# cpu_board.net
KiCad netlist of a schematic drawn in Altium Designer
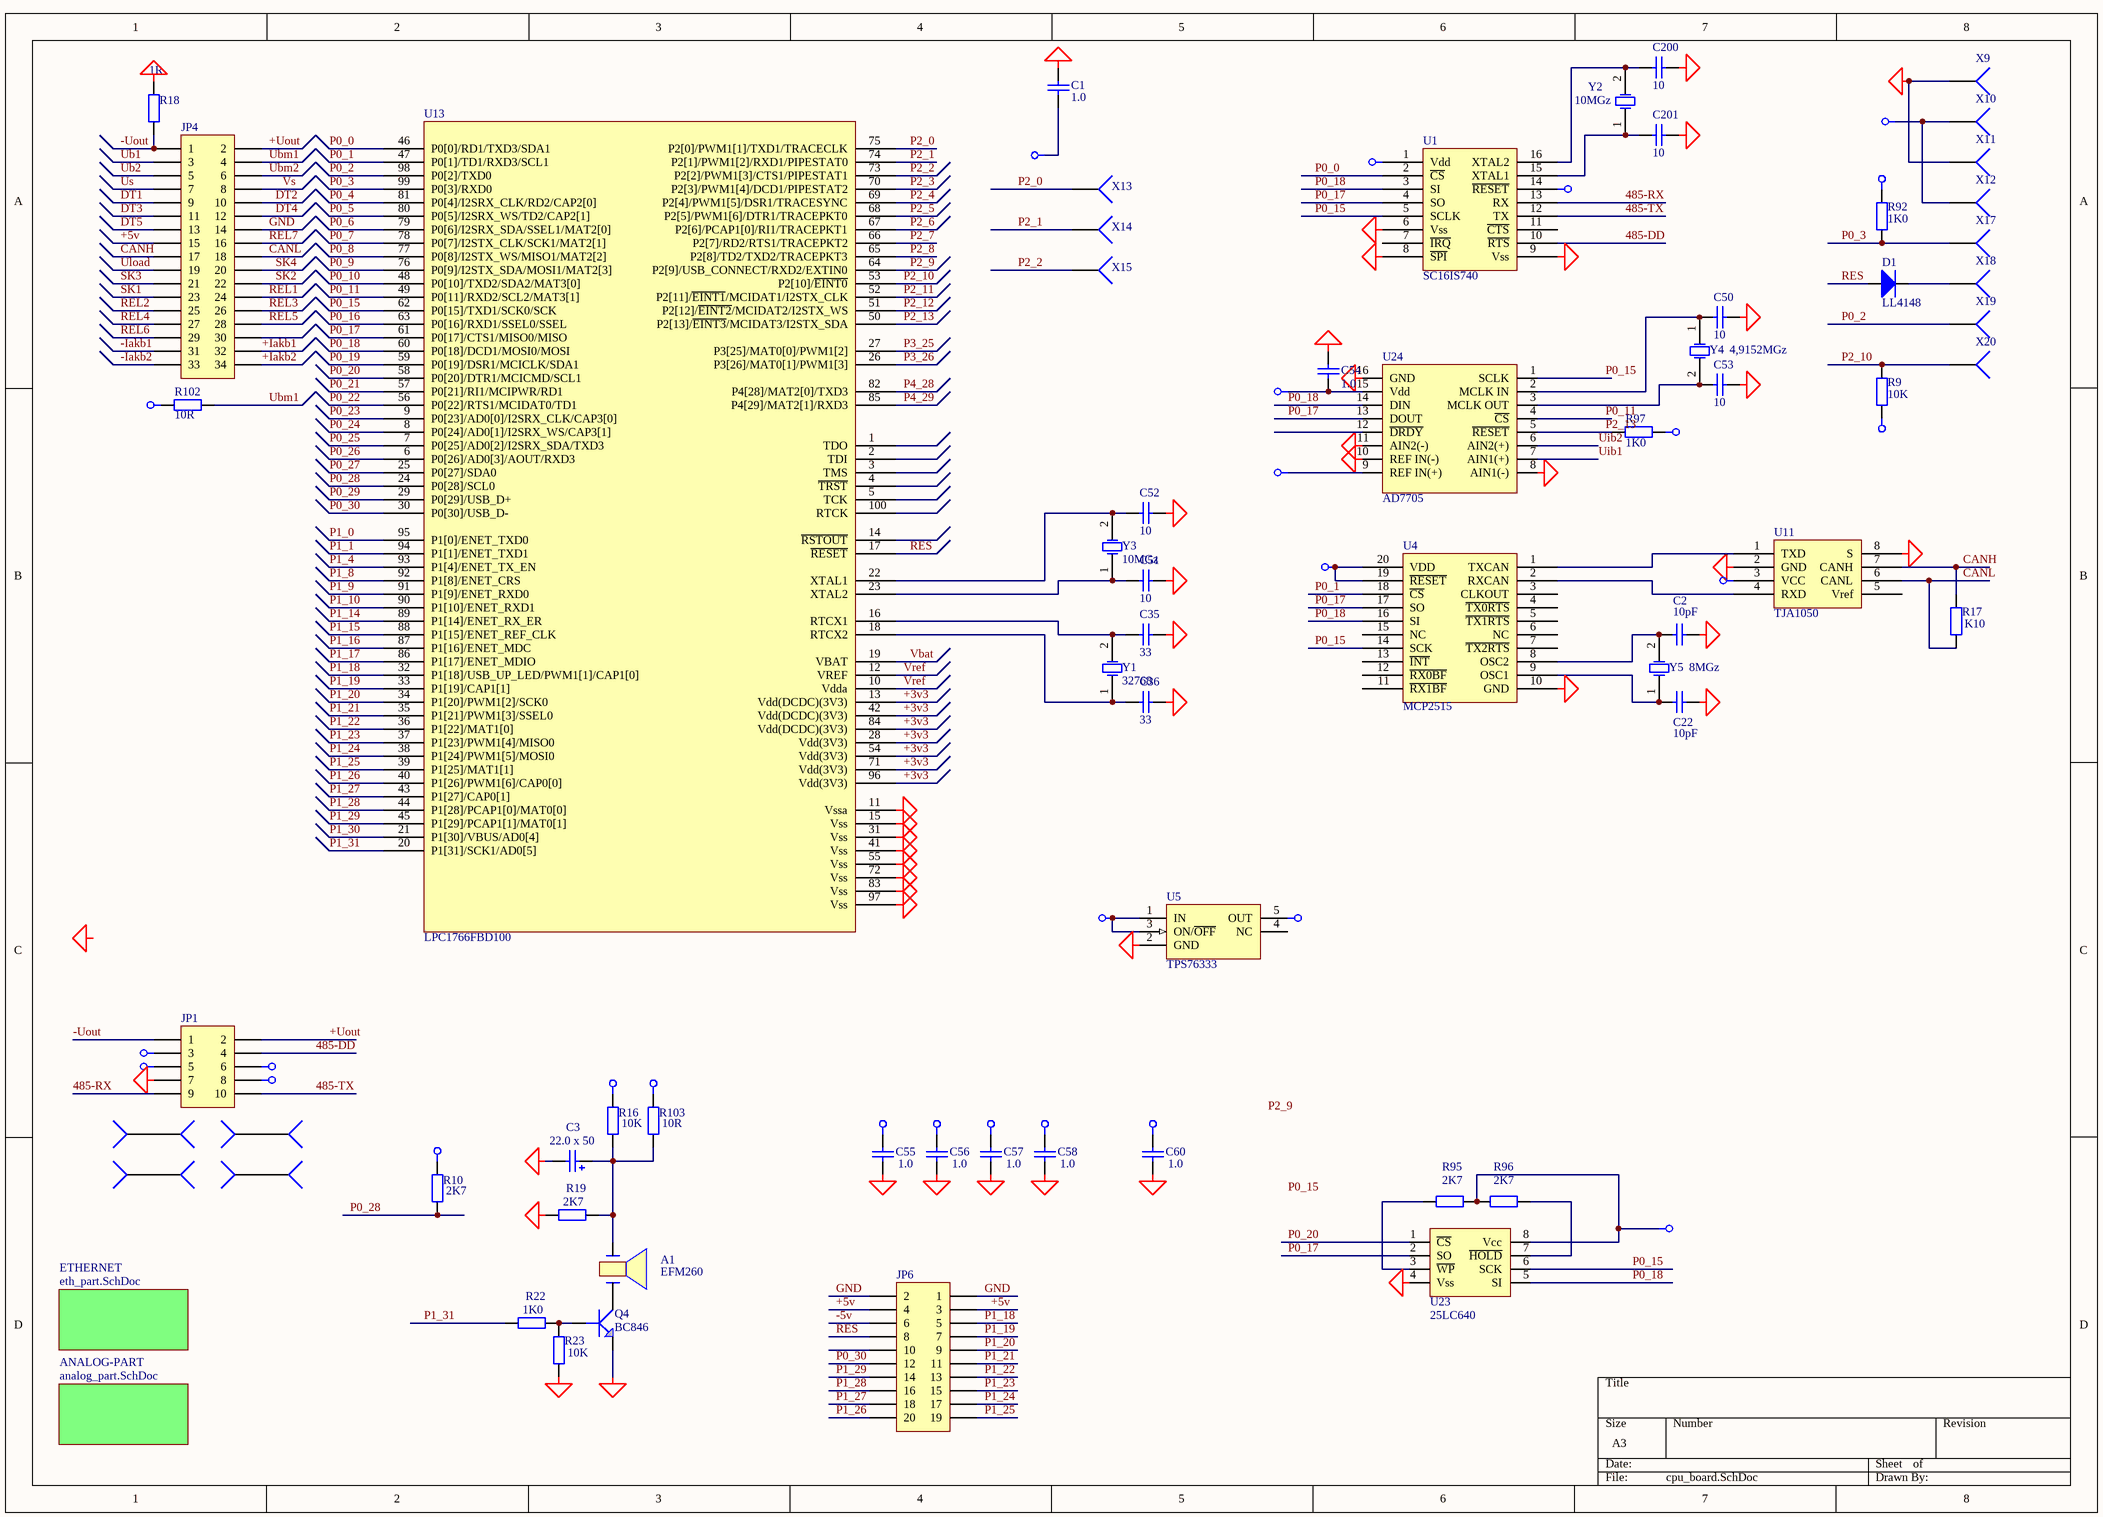
[diagram p0: cpu_board.SchDoc]

(export (version "E")
  (design (tool "Eeschema 10.0.6"))
  (components
    (comp (ref "A1")
      (value "EFM260")
      (footprint "Pjezo15")
      (description "Beeper")
      (libsource (lib "PAL") (part "PJEZ0"))
    )
    (comp (ref "C1")
      (value "1.0")
      (footprint "_1206")
      (description "Capacitor")
      (fields (field (name "MANUFACTURER") "Generic Components") (field (name "PUBLISHER") "Altium Limited"))
      (libsource (lib "Miscellaneous Devices") (part "Cap Semi"))
    )
    (comp (ref "C2")
      (value "Cap Semi")
      (footprint "_1206")
      (description "Capacitor (Semiconductor SIM Model)")
      (fields
        (field (name "MANUFACTURER") "Generic Components")
        (field (name "ALTIUM_VALUE") "10pF")
        (field (name "PUBLISHER") "Altium Limited")
      )
      (libsource (lib "Miscellaneous Devices") (part "Cap Semi"))
    )
    (comp (ref "C3")
      (value "22.0 x 50")
      (footprint "el3")
      (description "Polarized Capacitor (Radial)")
      (fields (field (name "MANUFACTURER") "Generic Components") (field (name "PUBLISHER") "Altium Limited"))
      (libsource (lib "PAL") (part "Cap Pol1"))
    )
    (comp (ref "C22")
      (value "Cap Semi")
      (footprint "_1206")
      (description "Capacitor (Semiconductor SIM Model)")
      (fields
        (field (name "MANUFACTURER") "Generic Components")
        (field (name "ALTIUM_VALUE") "10pF")
        (field (name "PUBLISHER") "Altium Limited")
      )
      (libsource (lib "Miscellaneous Devices") (part "Cap Semi"))
    )
    (comp (ref "C35")
      (value "33")
      (footprint "_1206")
      (description "Capacitor (Semiconductor SIM Model)")
      (fields (field (name "MANUFACTURER") "Generic Components") (field (name "PUBLISHER") "Altium Limited"))
      (libsource (lib "Miscellaneous Devices") (part "Cap Semi"))
    )
    (comp (ref "C36")
      (value "33")
      (footprint "_1206")
      (description "Capacitor (Semiconductor SIM Model)")
      (fields (field (name "MANUFACTURER") "Generic Components") (field (name "PUBLISHER") "Altium Limited"))
      (libsource (lib "Miscellaneous Devices") (part "Cap Semi"))
    )
    (comp (ref "C50")
      (value "10")
      (footprint "_1206")
      (description "Capacitor")
      (fields (field (name "MANUFACTURER") "Generic Components") (field (name "PUBLISHER") "Altium Limited"))
      (libsource (lib "") (part "Cap Semi_1"))
    )
    (comp (ref "C51")
      (value "10")
      (footprint "_1206")
      (description "Capacitor")
      (fields (field (name "MANUFACTURER") "Generic Components") (field (name "PUBLISHER") "Altium Limited"))
      (libsource (lib "Miscellaneous Devices") (part "Cap Semi"))
    )
    (comp (ref "C52")
      (value "10")
      (footprint "_1206")
      (description "Capacitor")
      (fields (field (name "MANUFACTURER") "Generic Components") (field (name "PUBLISHER") "Altium Limited"))
      (libsource (lib "Miscellaneous Devices") (part "Cap Semi"))
    )
    (comp (ref "C53")
      (value "10")
      (footprint "_1206")
      (description "Capacitor")
      (fields (field (name "MANUFACTURER") "Generic Components") (field (name "PUBLISHER") "Altium Limited"))
      (libsource (lib "") (part "Cap Semi_1"))
    )
    (comp (ref "C54")
      (value "1.0")
      (footprint "_1206")
      (description "Capacitor")
      (fields (field (name "MANUFACTURER") "Generic Components") (field (name "PUBLISHER") "Altium Limited"))
      (libsource (lib "Miscellaneous Devices") (part "Cap Semi"))
    )
    (comp (ref "C55")
      (value "1.0")
      (footprint "_1206")
      (description "Capacitor")
      (fields (field (name "MANUFACTURER") "Generic Components") (field (name "PUBLISHER") "Altium Limited"))
      (libsource (lib "Miscellaneous Devices") (part "Cap Semi"))
    )
    (comp (ref "C56")
      (value "1.0")
      (footprint "_1206")
      (description "Capacitor")
      (fields (field (name "MANUFACTURER") "Generic Components") (field (name "PUBLISHER") "Altium Limited"))
      (libsource (lib "Miscellaneous Devices") (part "Cap Semi"))
    )
    (comp (ref "C57")
      (value "1.0")
      (footprint "_1206")
      (description "Capacitor")
      (fields (field (name "MANUFACTURER") "Generic Components") (field (name "PUBLISHER") "Altium Limited"))
      (libsource (lib "Miscellaneous Devices") (part "Cap Semi"))
    )
    (comp (ref "C58")
      (value "1.0")
      (footprint "_1206")
      (description "Capacitor")
      (fields (field (name "MANUFACTURER") "Generic Components") (field (name "PUBLISHER") "Altium Limited"))
      (libsource (lib "Miscellaneous Devices") (part "Cap Semi"))
    )
    (comp (ref "C60")
      (value "1.0")
      (footprint "_1206")
      (description "Capacitor")
      (fields (field (name "MANUFACTURER") "Generic Components") (field (name "PUBLISHER") "Altium Limited"))
      (libsource (lib "Miscellaneous Devices") (part "Cap Semi"))
    )
    (comp (ref "C200")
      (value "10")
      (footprint "_1206")
      (description "Capacitor")
      (fields (field (name "MANUFACTURER") "Generic Components") (field (name "PUBLISHER") "Altium Limited"))
      (libsource (lib "Miscellaneous Devices") (part "Cap Semi"))
    )
    (comp (ref "C201")
      (value "10")
      (footprint "_1206")
      (description "Capacitor")
      (fields (field (name "MANUFACTURER") "Generic Components") (field (name "PUBLISHER") "Altium Limited"))
      (libsource (lib "Miscellaneous Devices") (part "Cap Semi"))
    )
    (comp (ref "D1")
      (value "LL4148")
      (footprint "_1206d")
      (description "Diode")
      (fields (field (name "MANUFACTURER") "Generic Components") (field (name "PUBLISHER") "Altium Limited"))
      (libsource (lib "PAL") (part "Diode"))
    )
    (comp (ref "JP1")
      (value "PBD-10")
      (footprint "HDR2X5")
      (description "Header, 5-Pin, Dual row")
      (fields (field (name "MANUFACTURER") "Generic Components") (field (name "PUBLISHER") "Altium Limited"))
      (libsource (lib "Miscellaneous Connectors") (part "Header 5X2"))
    )
    (comp (ref "JP4")
      (value "IDC34")
      (footprint "IDC34M")
      (description "Header, 17-Pin, Dual row")
      (fields (field (name "MANUFACTURER") "Generic Components") (field (name "PUBLISHER") "Altium Limited"))
      (libsource (lib "Miscellaneous Connectors") (part "Header 17X2"))
    )
    (comp (ref "JP6")
      (value "PBD-20")
      (footprint "HDR2X10")
      (description "Header, 10-Pin, Dual row")
      (fields (field (name "MANUFACTURER") "Generic Components") (field (name "PUBLISHER") "Altium Limited"))
      (libsource (lib "Miscellaneous Connectors") (part "Header 10X2"))
    )
    (comp (ref "Q4")
      (value "BC846")
      (footprint "SO-G3")
      (description "Bipolar transistor")
      (libsource (lib "MAIN") (part "GT122"))
    )
    (comp (ref "R9")
      (value "10K")
      (footprint "_1206")
      (description "Resistor")
      (fields (field (name "MANUFACTURER") "Generic Components") (field (name "PUBLISHER") "Altium Limited"))
      (libsource (lib "Miscellaneous Devices") (part "Res2"))
    )
    (comp (ref "R10")
      (value "2K7")
      (footprint "_1206")
      (description "Resistor")
      (fields (field (name "MANUFACTURER") "Generic Components") (field (name "PUBLISHER") "Altium Limited"))
      (libsource (lib "Miscellaneous Devices") (part "Res2"))
    )
    (comp (ref "R16")
      (value "10K")
      (footprint "_1206")
      (description "Resistor")
      (fields (field (name "MANUFACTURER") "Generic Components") (field (name "PUBLISHER") "Altium Limited"))
      (libsource (lib "Miscellaneous Devices") (part "Res2"))
    )
    (comp (ref "R17")
      (value "K10")
      (footprint "_1206")
      (description "Resistor")
      (fields (field (name "MANUFACTURER") "Generic Components") (field (name "PUBLISHER") "Altium Limited"))
      (libsource (lib "Miscellaneous Devices") (part "Res2"))
    )
    (comp (ref "R18")
      (value "1R")
      (footprint "_1206")
      (description "Resistor")
      (fields (field (name "MANUFACTURER") "Generic Components") (field (name "PUBLISHER") "Altium Limited"))
      (libsource (lib "Miscellaneous Devices") (part "Res2"))
    )
    (comp (ref "R19")
      (value "2K7")
      (footprint "_1206")
      (description "Resistor")
      (fields (field (name "MANUFACTURER") "Generic Components") (field (name "PUBLISHER") "Altium Limited"))
      (libsource (lib "") (part "Res2_1"))
    )
    (comp (ref "R22")
      (value "1K0")
      (footprint "_1206")
      (description "Resistor")
      (fields (field (name "MANUFACTURER") "Generic Components") (field (name "PUBLISHER") "Altium Limited"))
      (libsource (lib "") (part "Res2_1"))
    )
    (comp (ref "R23")
      (value "10K")
      (footprint "_1206")
      (description "Resistor")
      (fields (field (name "MANUFACTURER") "Generic Components") (field (name "PUBLISHER") "Altium Limited"))
      (libsource (lib "Miscellaneous Devices") (part "Res2"))
    )
    (comp (ref "R92")
      (value "1K0")
      (footprint "_1206")
      (description "Resistor")
      (fields (field (name "MANUFACTURER") "Generic Components") (field (name "PUBLISHER") "Altium Limited"))
      (libsource (lib "") (part "Res2_1"))
    )
    (comp (ref "R95")
      (value "2K7")
      (footprint "_1206")
      (description "Resistor")
      (fields (field (name "MANUFACTURER") "Generic Components") (field (name "PUBLISHER") "Altium Limited"))
      (libsource (lib "") (part "Res2_1"))
    )
    (comp (ref "R96")
      (value "2K7")
      (footprint "_1206")
      (description "Resistor")
      (fields (field (name "MANUFACTURER") "Generic Components") (field (name "PUBLISHER") "Altium Limited"))
      (libsource (lib "") (part "Res2_1"))
    )
    (comp (ref "R97")
      (value "1K0")
      (footprint "_1206")
      (description "Resistor")
      (fields (field (name "MANUFACTURER") "Generic Components") (field (name "PUBLISHER") "Altium Limited"))
      (libsource (lib "Miscellaneous Devices") (part "Res2"))
    )
    (comp (ref "R102")
      (value "10R")
      (footprint "_1206")
      (description "Resistor")
      (fields (field (name "MANUFACTURER") "Generic Components") (field (name "PUBLISHER") "Altium Limited"))
      (libsource (lib "") (part "Res2_2"))
    )
    (comp (ref "R103")
      (value "10R")
      (footprint "_1206")
      (description "Resistor")
      (fields (field (name "MANUFACTURER") "Generic Components") (field (name "PUBLISHER") "Altium Limited"))
      (libsource (lib "Miscellaneous Devices") (part "Res2"))
    )
    (comp (ref "U1") (value "SC16IS740") (footprint "SO-G16") (libsource (lib "PAL") (part "SC16IS740")))
    (comp (ref "U4")
      (value "MCP2515")
      (footprint "TSSO6X6-G20/D6.6")
      (libsource (lib "PAL") (part "MCP2515"))
    )
    (comp (ref "U5")
      (value "TPS76333")
      (footprint "SO-G5/P.95")
      (description "Voltage Regulator")
      (fields
        (field (name "MANUFACTURER") "National Semiconductor")
        (field (name "PUBLISHER") "Altium Limited")
      )
      (libsource (lib "NSC Power Mgt Voltage Regulator") (part "LP2980AIM5-3.3"))
    )
    (comp (ref "U11") (value "TJA1050") (footprint "SO-G8/D5") (libsource (lib "PAL") (part "TJA1050")))
    (comp (ref "U13")
      (value "LPC1766FBD100")
      (footprint "LPC2368")
      (libsource (lib "PAL") (part "LPC2368FBD100"))
    )
    (comp (ref "U23")
      (value "25LC640")
      (footprint "SO-G8/D5")
      (description "Memory")
      (libsource (lib "PAL") (part "25LC640"))
    )
    (comp (ref "U24")
      (value "AD7705")
      (footprint "SO-G16/D10.4")
      (description "ADC")
      (libsource (lib "PAL") (part "AD7705"))
    )
    (comp (ref "X9")
      (value "~")
      (footprint "PIN1")
      (description "Socket")
      (fields (field (name "MANUFACTURER") "Generic Components") (field (name "PUBLISHER") "Altium Limited"))
      (libsource (lib "Miscellaneous Connectors") (part "Socket"))
    )
    (comp (ref "X10")
      (value "~")
      (footprint "PIN1")
      (description "Socket")
      (fields (field (name "MANUFACTURER") "Generic Components") (field (name "PUBLISHER") "Altium Limited"))
      (libsource (lib "Miscellaneous Connectors") (part "Socket"))
    )
    (comp (ref "X11")
      (value "~")
      (footprint "PIN1")
      (description "Socket")
      (fields (field (name "MANUFACTURER") "Generic Components") (field (name "PUBLISHER") "Altium Limited"))
      (libsource (lib "Miscellaneous Connectors") (part "Socket"))
    )
    (comp (ref "X12")
      (value "~")
      (footprint "PIN1")
      (description "Socket")
      (fields (field (name "MANUFACTURER") "Generic Components") (field (name "PUBLISHER") "Altium Limited"))
      (libsource (lib "Miscellaneous Connectors") (part "Socket"))
    )
    (comp (ref "X13")
      (value "~")
      (footprint "PIN1")
      (description "Socket")
      (fields (field (name "MANUFACTURER") "Generic Components") (field (name "PUBLISHER") "Altium Limited"))
      (libsource (lib "Miscellaneous Connectors") (part "Socket"))
    )
    (comp (ref "X14")
      (value "~")
      (footprint "PIN1")
      (description "Socket")
      (fields (field (name "MANUFACTURER") "Generic Components") (field (name "PUBLISHER") "Altium Limited"))
      (libsource (lib "Miscellaneous Connectors") (part "Socket"))
    )
    (comp (ref "X15")
      (value "~")
      (footprint "PIN1")
      (description "Socket")
      (fields (field (name "MANUFACTURER") "Generic Components") (field (name "PUBLISHER") "Altium Limited"))
      (libsource (lib "Miscellaneous Connectors") (part "Socket"))
    )
    (comp (ref "X16")
      (value "~")
      (footprint "PIN1")
      (description "Socket")
      (fields (field (name "MANUFACTURER") "Generic Components") (field (name "PUBLISHER") "Altium Limited"))
      (libsource (lib "Miscellaneous Connectors") (part "Socket"))
    )
    (comp (ref "X17")
      (value "~")
      (footprint "PIN1")
      (description "Socket")
      (fields (field (name "MANUFACTURER") "Generic Components") (field (name "PUBLISHER") "Altium Limited"))
      (libsource (lib "Miscellaneous Connectors") (part "Socket"))
    )
    (comp (ref "X18")
      (value "~")
      (footprint "PIN1")
      (description "Socket")
      (fields (field (name "MANUFACTURER") "Generic Components") (field (name "PUBLISHER") "Altium Limited"))
      (libsource (lib "Miscellaneous Connectors") (part "Socket"))
    )
    (comp (ref "X19")
      (value "~")
      (footprint "PIN1")
      (description "Socket")
      (fields (field (name "MANUFACTURER") "Generic Components") (field (name "PUBLISHER") "Altium Limited"))
      (libsource (lib "Miscellaneous Connectors") (part "Socket"))
    )
    (comp (ref "X20")
      (value "~")
      (footprint "PIN1")
      (description "Socket")
      (fields (field (name "MANUFACTURER") "Generic Components") (field (name "PUBLISHER") "Altium Limited"))
      (libsource (lib "Miscellaneous Connectors") (part "Socket"))
    )
    (comp (ref "X21")
      (value "~")
      (footprint "PIN1")
      (description "Socket")
      (fields (field (name "MANUFACTURER") "Generic Components") (field (name "PUBLISHER") "Altium Limited"))
      (libsource (lib "Miscellaneous Connectors") (part "Socket"))
    )
    (comp (ref "X22")
      (value "~")
      (footprint "PIN1")
      (description "Socket")
      (fields (field (name "MANUFACTURER") "Generic Components") (field (name "PUBLISHER") "Altium Limited"))
      (libsource (lib "Miscellaneous Connectors") (part "Socket"))
    )
    (comp (ref "X23")
      (value "~")
      (footprint "PIN1")
      (description "Socket")
      (fields (field (name "MANUFACTURER") "Generic Components") (field (name "PUBLISHER") "Altium Limited"))
      (libsource (lib "Miscellaneous Connectors") (part "Socket"))
    )
    (comp (ref "X24")
      (value "~")
      (footprint "PIN1")
      (description "Socket")
      (fields (field (name "MANUFACTURER") "Generic Components") (field (name "PUBLISHER") "Altium Limited"))
      (libsource (lib "Miscellaneous Connectors") (part "Socket"))
    )
    (comp (ref "X25")
      (value "~")
      (footprint "PIN1")
      (description "Socket")
      (fields (field (name "MANUFACTURER") "Generic Components") (field (name "PUBLISHER") "Altium Limited"))
      (libsource (lib "Miscellaneous Connectors") (part "Socket"))
    )
    (comp (ref "X26")
      (value "~")
      (footprint "PIN1")
      (description "Socket")
      (fields (field (name "MANUFACTURER") "Generic Components") (field (name "PUBLISHER") "Altium Limited"))
      (libsource (lib "Miscellaneous Connectors") (part "Socket"))
    )
    (comp (ref "X27")
      (value "~")
      (footprint "PIN1")
      (description "Socket")
      (fields (field (name "MANUFACTURER") "Generic Components") (field (name "PUBLISHER") "Altium Limited"))
      (libsource (lib "Miscellaneous Connectors") (part "Socket"))
    )
    (comp (ref "Y1")
      (value "32768")
      (footprint "QWARZ2")
      (description "Crystal Oscillator")
      (fields (field (name "MANUFACTURER") "Generic Components") (field (name "PUBLISHER") "Altium Limited"))
      (libsource (lib "Miscellaneous Devices") (part "XTAL"))
    )
    (comp (ref "Y2")
      (value "10MGz")
      (footprint "QWARZ1")
      (description "Crystal Oscillator")
      (fields (field (name "MANUFACTURER") "Generic Components") (field (name "PUBLISHER") "Altium Limited"))
      (libsource (lib "Miscellaneous Devices") (part "XTAL"))
    )
    (comp (ref "Y3")
      (value "10MGz")
      (footprint "QWARZ1")
      (description "Crystal Oscillator")
      (fields (field (name "MANUFACTURER") "Generic Components") (field (name "PUBLISHER") "Altium Limited"))
      (libsource (lib "Miscellaneous Devices") (part "XTAL"))
    )
    (comp (ref "Y4")
      (value "4,9152MGz")
      (footprint "QWARZ1")
      (description "Crystal Oscillator")
      (fields (field (name "MANUFACTURER") "Generic Components") (field (name "PUBLISHER") "Altium Limited"))
      (libsource (lib "") (part "XTAL_1"))
    )
    (comp (ref "Y5")
      (value "8MGz")
      (footprint "QWARZ1")
      (description "Crystal Oscillator")
      (fields (field (name "MANUFACTURER") "Generic Components") (field (name "PUBLISHER") "Altium Limited"))
      (libsource (lib "Miscellaneous Devices") (part "XTAL"))
    )
  )
  (nets
    (net (code "1") (name "+3v3") (class "Default")
      (node (ref "C1") (pin "1") (pinfunction "1_1") (pintype "passive"))
      (node (ref "C58") (pin "2") (pinfunction "2_2") (pintype "passive"))
      (node (ref "JP1") (pin "3") (pinfunction "3_3") (pintype "passive"))
      (node (ref "R10") (pin "2") (pinfunction "2_2") (pintype "passive"))
      (node (ref "R9") (pin "1") (pinfunction "1_1") (pintype "passive"))
      (node (ref "R92") (pin "2") (pinfunction "2_2") (pintype "passive"))
      (node (ref "U13") (pin "13") (pinfunction "Vdd(DCDC)(3V3)_13") (pintype "passive"))
      (node (ref "U13") (pin "28") (pinfunction "Vdd(3V3)_28") (pintype "passive"))
      (node (ref "U13") (pin "42") (pinfunction "Vdd(DCDC)(3V3)_42") (pintype "passive"))
      (node (ref "U13") (pin "54") (pinfunction "Vdd(3V3)_54") (pintype "passive"))
      (node (ref "U13") (pin "71") (pinfunction "Vdd(3V3)_71") (pintype "passive"))
      (node (ref "U13") (pin "84") (pinfunction "Vdd(DCDC)(3V3)_84") (pintype "passive"))
      (node (ref "U13") (pin "96") (pinfunction "Vdd(3V3)_96") (pintype "passive"))
    )
    (net (code "2") (name "+5v") (class "Default")
      (node (ref "C54") (pin "2") (pinfunction "2_2") (pintype "passive"))
      (node (ref "C55") (pin "2") (pinfunction "2_2") (pintype "passive"))
      (node (ref "C57") (pin "2") (pinfunction "2_2") (pintype "passive"))
      (node (ref "C60") (pin "2") (pinfunction "2_2") (pintype "passive"))
      (node (ref "JP1") (pin "5") (pinfunction "5_5") (pintype "passive"))
      (node (ref "JP4") (pin "15") (pinfunction "15_15") (pintype "passive"))
      (node (ref "JP6") (pin "3") (pinfunction "3_3") (pintype "passive"))
      (node (ref "JP6") (pin "4") (pinfunction "4_4") (pintype "passive"))
      (node (ref "R103") (pin "2") (pinfunction "2_2") (pintype "passive"))
      (node (ref "R95") (pin "2") (pinfunction "2_2") (pintype "passive"))
      (node (ref "R96") (pin "1") (pinfunction "1_1") (pintype "passive"))
      (node (ref "R97") (pin "2") (pinfunction "2_2") (pintype "passive"))
      (node (ref "U1") (pin "1") (pinfunction "Vdd_1") (pintype "passive"))
      (node (ref "U1") (pin "14") (pinfunction "~{RESET}_14") (pintype "passive"))
      (node (ref "U11") (pin "3") (pinfunction "VCC_3") (pintype "passive"))
      (node (ref "U23") (pin "8") (pinfunction "Vcc_8") (pintype "passive"))
      (node (ref "U24") (pin "15") (pinfunction "Vdd_15") (pintype "passive"))
      (node (ref "U4") (pin "19") (pinfunction "~{RESET}_19") (pintype "passive"))
      (node (ref "U4") (pin "20") (pinfunction "VDD_20") (pintype "passive"))
      (node (ref "U5") (pin "1") (pinfunction "IN_1") (pintype "power_in"))
      (node (ref "U5") (pin "3") (pinfunction "ON/~{OFF}_3") (pintype "input"))
      (node (ref "X10") (pin "1") (pinfunction "1_1") (pintype "passive"))
      (node (ref "X12") (pin "1") (pinfunction "1_1") (pintype "passive"))
    )
    (net (code "3") (name "+Uout") (class "Default")
      (node (ref "JP1") (pin "2") (pinfunction "2_2") (pintype "passive"))
      (node (ref "JP4") (pin "2") (pinfunction "2_2") (pintype "passive"))
      (node (ref "R102") (pin "2") (pinfunction "2_2") (pintype "passive"))
      (node (ref "R16") (pin "2") (pinfunction "2_2") (pintype "passive"))
    )
    (net (code "4") (name "-5v") (class "Default")
      (node (ref "C56") (pin "2") (pinfunction "2_2") (pintype "passive"))
      (node (ref "JP1") (pin "8") (pinfunction "8_8") (pintype "passive"))
      (node (ref "JP6") (pin "6") (pinfunction "6_6") (pintype "passive"))
    )
    (net (code "5") (name "/+Iakb1") (class "Default")
      (node (ref "JP4") (pin "32") (pinfunction "32_32") (pintype "passive"))
    )
    (net (code "6") (name "/+Iakb2") (class "Default")
      (node (ref "JP4") (pin "34") (pinfunction "34_34") (pintype "passive"))
    )
    (net (code "7") (name "/-Iakb1") (class "Default")
      (node (ref "JP4") (pin "31") (pinfunction "31_31") (pintype "passive"))
    )
    (net (code "8") (name "/-Iakb2") (class "Default")
      (node (ref "JP4") (pin "33") (pinfunction "33_33") (pintype "passive"))
    )
    (net (code "9") (name "/-Uout") (class "Default")
      (node (ref "JP1") (pin "1") (pinfunction "1_1") (pintype "passive"))
      (node (ref "JP4") (pin "1") (pinfunction "1_1") (pintype "passive"))
      (node (ref "R18") (pin "1") (pinfunction "1_1") (pintype "passive"))
    )
    (net (code "10") (name "/485-DD") (class "Default")
      (node (ref "JP1") (pin "4") (pinfunction "4_4") (pintype "passive"))
      (node (ref "U1") (pin "10") (pinfunction "~{RTS}_10") (pintype "passive"))
    )
    (net (code "11") (name "/485-RX") (class "Default")
      (node (ref "JP1") (pin "9") (pinfunction "9_9") (pintype "passive"))
      (node (ref "U1") (pin "13") (pinfunction "RX_13") (pintype "passive"))
    )
    (net (code "12") (name "/485-TX") (class "Default")
      (node (ref "JP1") (pin "10") (pinfunction "10_10") (pintype "passive"))
      (node (ref "U1") (pin "12") (pinfunction "TX_12") (pintype "passive"))
    )
    (net (code "13") (name "/CANH") (class "Default")
      (node (ref "JP4") (pin "17") (pinfunction "17_17") (pintype "passive"))
      (node (ref "R17") (pin "2") (pinfunction "2_2") (pintype "passive"))
      (node (ref "U11") (pin "7") (pinfunction "CANH_7") (pintype "passive"))
    )
    (net (code "14") (name "/CANL") (class "Default")
      (node (ref "JP4") (pin "18") (pinfunction "18_18") (pintype "passive"))
      (node (ref "R17") (pin "1") (pinfunction "1_1") (pintype "passive"))
      (node (ref "U11") (pin "6") (pinfunction "CANL_6") (pintype "passive"))
    )
    (net (code "15") (name "/DT1") (class "Default")
      (node (ref "JP4") (pin "9") (pinfunction "9_9") (pintype "passive"))
    )
    (net (code "16") (name "/DT2") (class "Default")
      (node (ref "JP4") (pin "10") (pinfunction "10_10") (pintype "passive"))
    )
    (net (code "17") (name "/DT3") (class "Default")
      (node (ref "JP4") (pin "11") (pinfunction "11_11") (pintype "passive"))
    )
    (net (code "18") (name "/DT4") (class "Default")
      (node (ref "JP4") (pin "12") (pinfunction "12_12") (pintype "passive"))
    )
    (net (code "19") (name "/DT5") (class "Default")
      (node (ref "JP4") (pin "13") (pinfunction "13_13") (pintype "passive"))
    )
    (net (code "20") (name "/P0_0") (class "Default")
      (node (ref "U1") (pin "2") (pinfunction "~{CS}_2") (pintype "passive"))
      (node (ref "U13") (pin "46") (pinfunction "P0[0]/RD1/TXD3/SDA1_46") (pintype "passive"))
    )
    (net (code "21") (name "/P0_1") (class "Default")
      (node (ref "U13") (pin "47") (pinfunction "P0[1]/TD1/RXD3/SCL1_47") (pintype "passive"))
      (node (ref "U4") (pin "18") (pinfunction "~{CS}_18") (pintype "passive"))
    )
    (net (code "22") (name "/P0_2") (class "Default")
      (node (ref "U13") (pin "98") (pinfunction "P0[2]/TXD0_98") (pintype "passive"))
      (node (ref "X19") (pin "1") (pinfunction "1_1") (pintype "passive"))
    )
    (net (code "23") (name "/P0_3") (class "Default")
      (node (ref "R92") (pin "1") (pinfunction "1_1") (pintype "passive"))
      (node (ref "U13") (pin "99") (pinfunction "P0[3]/RXD0_99") (pintype "passive"))
      (node (ref "X17") (pin "1") (pinfunction "1_1") (pintype "passive"))
    )
    (net (code "24") (name "/P0_4") (class "Default")
      (node (ref "U13") (pin "81") (pinfunction "P0[4]/I2SRX_CLK/RD2/CAP2[0]_81") (pintype "passive"))
    )
    (net (code "25") (name "/P0_5") (class "Default")
      (node (ref "U13") (pin "80") (pinfunction "P0[5]/I2SRX_WS/TD2/CAP2[1]_80") (pintype "passive"))
    )
    (net (code "26") (name "/P0_6") (class "Default")
      (node (ref "U13") (pin "79") (pinfunction "P0[6]/I2SRX_SDA/SSEL1/MAT2[0]_79") (pintype "passive"))
    )
    (net (code "27") (name "/P0_7") (class "Default")
      (node (ref "U13") (pin "78") (pinfunction "P0[7]/I2STX_CLK/SCK1/MAT2[1]_78") (pintype "passive"))
    )
    (net (code "28") (name "/P0_8") (class "Default")
      (node (ref "U13") (pin "77") (pinfunction "P0[8]/I2STX_WS/MISO1/MAT2[2]_77") (pintype "passive"))
    )
    (net (code "29") (name "/P0_9") (class "Default")
      (node (ref "U13") (pin "76") (pinfunction "P0[9]/I2STX_SDA/MOSI1/MAT2[3]_76") (pintype "passive"))
    )
    (net (code "30") (name "/P0_10") (class "Default")
      (node (ref "U13") (pin "48") (pinfunction "P0[10]/TXD2/SDA2/MAT3[0]_48") (pintype "passive"))
    )
    (net (code "31") (name "/P0_11") (class "Default")
      (node (ref "U13") (pin "49") (pinfunction "P0[11]/RXD2/SCL2/MAT3[1]_49") (pintype "passive"))
      (node (ref "U24") (pin "4") (pinfunction "~{CS}_4") (pintype "passive"))
    )
    (net (code "32") (name "/P0_15") (class "Default")
      (node (ref "U1") (pin "5") (pinfunction "SCLK_5") (pintype "passive"))
      (node (ref "U13") (pin "62") (pinfunction "P0[15]/TXD1/SCK0/SCK_62") (pintype "passive"))
      (node (ref "U23") (pin "6") (pinfunction "SCK_6") (pintype "passive"))
      (node (ref "U24") (pin "1") (pinfunction "SCLK_1") (pintype "passive"))
      (node (ref "U4") (pin "14") (pinfunction "SCK_14") (pintype "passive"))
    )
    (net (code "33") (name "/P0_16") (class "Default")
      (node (ref "U13") (pin "63") (pinfunction "P0[16]/RXD1/SSEL0/SSEL_63") (pintype "passive"))
    )
    (net (code "34") (name "/P0_17") (class "Default")
      (node (ref "U1") (pin "4") (pinfunction "SO_4") (pintype "passive"))
      (node (ref "U13") (pin "61") (pinfunction "P0[17]/CTS1/MISO0/MISO_61") (pintype "passive"))
      (node (ref "U23") (pin "2") (pinfunction "SO_2") (pintype "passive"))
      (node (ref "U24") (pin "13") (pinfunction "DOUT_13") (pintype "passive"))
      (node (ref "U4") (pin "17") (pinfunction "SO_17") (pintype "passive"))
    )
    (net (code "35") (name "/P0_18") (class "Default")
      (node (ref "U1") (pin "3") (pinfunction "SI_3") (pintype "passive"))
      (node (ref "U13") (pin "60") (pinfunction "P0[18]/DCD1/MOSI0/MOSI_60") (pintype "passive"))
      (node (ref "U23") (pin "5") (pinfunction "SI_5") (pintype "passive"))
      (node (ref "U24") (pin "14") (pinfunction "DIN_14") (pintype "passive"))
      (node (ref "U4") (pin "16") (pinfunction "SI_16") (pintype "passive"))
    )
    (net (code "36") (name "/P0_19") (class "Default")
      (node (ref "U13") (pin "59") (pinfunction "P0[19]/DSR1/MCICLK/SDA1_59") (pintype "passive"))
    )
    (net (code "37") (name "/P0_20") (class "Default")
      (node (ref "U13") (pin "58") (pinfunction "P0[20]/DTR1/MCICMD/SCL1_58") (pintype "passive"))
      (node (ref "U23") (pin "1") (pinfunction "~{CS}_1") (pintype "passive"))
    )
    (net (code "38") (name "/P0_21") (class "Default")
      (node (ref "U13") (pin "57") (pinfunction "P0[21]/RI1/MCIPWR/RD1_57") (pintype "passive"))
    )
    (net (code "39") (name "/P0_22") (class "Default")
      (node (ref "U13") (pin "56") (pinfunction "P0[22]/RTS1/MCIDAT0/TD1_56") (pintype "passive"))
    )
    (net (code "40") (name "/P0_23") (class "Default")
      (node (ref "U13") (pin "9") (pinfunction "P0[23]/AD0[0]/I2SRX_CLK/CAP3[0]_9") (pintype "passive"))
    )
    (net (code "41") (name "/P0_24") (class "Default")
      (node (ref "U13") (pin "8") (pinfunction "P0[24]/AD0[1]/I2SRX_WS/CAP3[1]_8") (pintype "passive"))
    )
    (net (code "42") (name "/P0_25") (class "Default")
      (node (ref "U13") (pin "7") (pinfunction "P0[25]/AD0[2]/I2SRX_SDA/TXD3_7") (pintype "passive"))
    )
    (net (code "43") (name "/P0_26") (class "Default")
      (node (ref "U13") (pin "6") (pinfunction "P0[26]/AD0[3]/AOUT/RXD3_6") (pintype "passive"))
    )
    (net (code "44") (name "/P0_27") (class "Default")
      (node (ref "U13") (pin "25") (pinfunction "P0[27]/SDA0_25") (pintype "passive"))
    )
    (net (code "45") (name "/P0_28") (class "Default")
      (node (ref "R10") (pin "1") (pinfunction "1_1") (pintype "passive"))
      (node (ref "U13") (pin "24") (pinfunction "P0[28]/SCL0_24") (pintype "passive"))
    )
    (net (code "46") (name "/P0_29") (class "Default")
      (node (ref "U13") (pin "29") (pinfunction "P0[29]/USB_D+_29") (pintype "passive"))
    )
    (net (code "47") (name "/P0_30") (class "Default")
      (node (ref "JP6") (pin "12") (pinfunction "12_12") (pintype "passive"))
      (node (ref "U13") (pin "30") (pinfunction "P0[30]/USB_D-_30") (pintype "passive"))
    )
    (net (code "48") (name "/P1_0") (class "Default")
      (node (ref "U13") (pin "95") (pinfunction "P1[0]/ENET_TXD0_95") (pintype "passive"))
    )
    (net (code "49") (name "/P1_1") (class "Default")
      (node (ref "U13") (pin "94") (pinfunction "P1[1]/ENET_TXD1_94") (pintype "passive"))
    )
    (net (code "50") (name "/P1_4") (class "Default")
      (node (ref "U13") (pin "93") (pinfunction "P1[4]/ENET_TX_EN_93") (pintype "passive"))
    )
    (net (code "51") (name "/P1_8") (class "Default")
      (node (ref "U13") (pin "92") (pinfunction "P1[8]/ENET_CRS_92") (pintype "passive"))
    )
    (net (code "52") (name "/P1_9") (class "Default")
      (node (ref "U13") (pin "91") (pinfunction "P1[9]/ENET_RXD0_91") (pintype "passive"))
    )
    (net (code "53") (name "/P1_10") (class "Default")
      (node (ref "U13") (pin "90") (pinfunction "P1[10]/ENET_RXD1_90") (pintype "passive"))
    )
    (net (code "54") (name "/P1_14") (class "Default")
      (node (ref "U13") (pin "89") (pinfunction "P1[14]/ENET_RX_ER_89") (pintype "passive"))
    )
    (net (code "55") (name "/P1_15") (class "Default")
      (node (ref "U13") (pin "88") (pinfunction "P1[15]/ENET_REF_CLK_88") (pintype "passive"))
    )
    (net (code "56") (name "/P1_16") (class "Default")
      (node (ref "U13") (pin "87") (pinfunction "P1[16]/ENET_MDC_87") (pintype "passive"))
    )
    (net (code "57") (name "/P1_17") (class "Default")
      (node (ref "U13") (pin "86") (pinfunction "P1[17]/ENET_MDIO_86") (pintype "passive"))
    )
    (net (code "58") (name "/P1_18") (class "Default")
      (node (ref "JP6") (pin "5") (pinfunction "5_5") (pintype "passive"))
      (node (ref "U13") (pin "32") (pinfunction "P1[18]/USB_UP_LED/PWM1[1]/CAP1[0]_32") (pintype "passive"))
    )
    (net (code "59") (name "/P1_19") (class "Default")
      (node (ref "JP6") (pin "7") (pinfunction "7_7") (pintype "passive"))
      (node (ref "U13") (pin "33") (pinfunction "P1[19]/CAP1[1]_33") (pintype "passive"))
    )
    (net (code "60") (name "/P1_20") (class "Default")
      (node (ref "JP6") (pin "9") (pinfunction "9_9") (pintype "passive"))
      (node (ref "U13") (pin "34") (pinfunction "P1[20]/PWM1[2]/SCK0_34") (pintype "passive"))
    )
    (net (code "61") (name "/P1_21") (class "Default")
      (node (ref "JP6") (pin "11") (pinfunction "11_11") (pintype "passive"))
      (node (ref "U13") (pin "35") (pinfunction "P1[21]/PWM1[3]/SSEL0_35") (pintype "passive"))
    )
    (net (code "62") (name "/P1_22") (class "Default")
      (node (ref "JP6") (pin "13") (pinfunction "13_13") (pintype "passive"))
      (node (ref "U13") (pin "36") (pinfunction "P1[22]/MAT1[0]_36") (pintype "passive"))
    )
    (net (code "63") (name "/P1_23") (class "Default")
      (node (ref "JP6") (pin "15") (pinfunction "15_15") (pintype "passive"))
      (node (ref "U13") (pin "37") (pinfunction "P1[23]/PWM1[4]/MISO0_37") (pintype "passive"))
    )
    (net (code "64") (name "/P1_24") (class "Default")
      (node (ref "JP6") (pin "17") (pinfunction "17_17") (pintype "passive"))
      (node (ref "U13") (pin "38") (pinfunction "P1[24]/PWM1[5]/MOSI0_38") (pintype "passive"))
    )
    (net (code "65") (name "/P1_25") (class "Default")
      (node (ref "JP6") (pin "19") (pinfunction "19_19") (pintype "passive"))
      (node (ref "U13") (pin "39") (pinfunction "P1[25]/MAT1[1]_39") (pintype "passive"))
    )
    (net (code "66") (name "/P1_26") (class "Default")
      (node (ref "JP6") (pin "20") (pinfunction "20_20") (pintype "passive"))
      (node (ref "U13") (pin "40") (pinfunction "P1[26]/PWM1[6]/CAP0[0]_40") (pintype "passive"))
    )
    (net (code "67") (name "/P1_27") (class "Default")
      (node (ref "JP6") (pin "18") (pinfunction "18_18") (pintype "passive"))
      (node (ref "U13") (pin "43") (pinfunction "P1[27]/CAP0[1]_43") (pintype "passive"))
    )
    (net (code "68") (name "/P1_28") (class "Default")
      (node (ref "JP6") (pin "16") (pinfunction "16_16") (pintype "passive"))
      (node (ref "U13") (pin "44") (pinfunction "P1[28]/PCAP1[0]/MAT0[0]_44") (pintype "passive"))
    )
    (net (code "69") (name "/P1_29") (class "Default")
      (node (ref "JP6") (pin "14") (pinfunction "14_14") (pintype "passive"))
      (node (ref "U13") (pin "45") (pinfunction "P1[29]/PCAP1[1]/MAT0[1]_45") (pintype "passive"))
    )
    (net (code "70") (name "/P1_30") (class "Default")
      (node (ref "U13") (pin "21") (pinfunction "P1[30]/VBUS/AD0[4]_21") (pintype "passive"))
    )
    (net (code "71") (name "/P1_31") (class "Default")
      (node (ref "R22") (pin "1") (pinfunction "1_1") (pintype "passive"))
      (node (ref "U13") (pin "20") (pinfunction "P1[31]/SCK1/AD0[5]_20") (pintype "passive"))
    )
    (net (code "72") (name "/P2_0") (class "Default")
      (node (ref "U13") (pin "75") (pinfunction "P2[0]/PWM1[1]/TXD1/TRACECLK_75") (pintype "passive"))
      (node (ref "X13") (pin "1") (pinfunction "1_1") (pintype "passive"))
    )
    (net (code "73") (name "/P2_1") (class "Default")
      (node (ref "U13") (pin "74") (pinfunction "P2[1]/PWM1[2]/RXD1/PIPESTAT0_74") (pintype "passive"))
      (node (ref "X14") (pin "1") (pinfunction "1_1") (pintype "passive"))
    )
    (net (code "74") (name "/P2_2") (class "Default")
      (node (ref "U13") (pin "73") (pinfunction "P2[2]/PWM1[3]/CTS1/PIPESTAT1_73") (pintype "passive"))
      (node (ref "X15") (pin "1") (pinfunction "1_1") (pintype "passive"))
    )
    (net (code "75") (name "/P2_3") (class "Default")
      (node (ref "U13") (pin "70") (pinfunction "P2[3]/PWM1[4]/DCD1/PIPESTAT2_70") (pintype "passive"))
    )
    (net (code "76") (name "/P2_4") (class "Default")
      (node (ref "U13") (pin "69") (pinfunction "P2[4]/PWM1[5]/DSR1/TRACESYNC_69") (pintype "passive"))
    )
    (net (code "77") (name "/P2_5") (class "Default")
      (node (ref "U13") (pin "68") (pinfunction "P2[5]/PWM1[6]/DTR1/TRACEPKT0_68") (pintype "passive"))
    )
    (net (code "78") (name "/P2_6") (class "Default")
      (node (ref "U13") (pin "67") (pinfunction "P2[6]/PCAP1[0]/RI1/TRACEPKT1_67") (pintype "passive"))
    )
    (net (code "79") (name "/P2_7") (class "Default")
      (node (ref "U13") (pin "66") (pinfunction "P2[7]/RD2/RTS1/TRACEPKT2_66") (pintype "passive"))
    )
    (net (code "80") (name "/P2_8") (class "Default")
      (node (ref "U13") (pin "65") (pinfunction "P2[8]/TD2/TXD2/TRACEPKT3_65") (pintype "passive"))
    )
    (net (code "81") (name "/P2_9") (class "Default")
      (node (ref "U13") (pin "64") (pinfunction "P2[9]/USB_CONNECT/RXD2/EXTIN0_64") (pintype "passive"))
    )
    (net (code "82") (name "/P2_10") (class "Default")
      (node (ref "R9") (pin "2") (pinfunction "2_2") (pintype "passive"))
      (node (ref "U13") (pin "53") (pinfunction "P2[10]/~{EINT0}_53") (pintype "passive"))
      (node (ref "X20") (pin "1") (pinfunction "1_1") (pintype "passive"))
    )
    (net (code "83") (name "/P2_11") (class "Default")
      (node (ref "U13") (pin "52") (pinfunction "P2[11]/~{EINT1}/MCIDAT1/I2STX_CLK_52") (pintype "passive"))
    )
    (net (code "84") (name "/P2_12") (class "Default")
      (node (ref "U13") (pin "51") (pinfunction "P2[12]/~{EINT2}/MCIDAT2/I2STX_WS_51") (pintype "passive"))
    )
    (net (code "85") (name "/P2_13") (class "Default")
      (node (ref "R97") (pin "1") (pinfunction "1_1") (pintype "passive"))
      (node (ref "U13") (pin "50") (pinfunction "P2[13]/~{EINT3}/MCIDAT3/I2STX_SDA_50") (pintype "passive"))
      (node (ref "U24") (pin "5") (pinfunction "~{RESET}_5") (pintype "passive"))
    )
    (net (code "86") (name "/P3_25") (class "Default")
      (node (ref "U13") (pin "27") (pinfunction "P3[25]/MAT0[0]/PWM1[2]_27") (pintype "passive"))
    )
    (net (code "87") (name "/P3_26") (class "Default")
      (node (ref "U13") (pin "26") (pinfunction "P3[26]/MAT0[1]/PWM1[3]_26") (pintype "passive"))
    )
    (net (code "88") (name "/P4_28") (class "Default")
      (node (ref "U13") (pin "82") (pinfunction "P4[28]/MAT2[0]/TXD3_82") (pintype "passive"))
    )
    (net (code "89") (name "/P4_29") (class "Default")
      (node (ref "U13") (pin "85") (pinfunction "P4[29]/MAT2[1]/RXD3_85") (pintype "passive"))
    )
    (net (code "90") (name "/REL1") (class "Default")
      (node (ref "JP4") (pin "24") (pinfunction "24_24") (pintype "passive"))
    )
    (net (code "91") (name "/REL2") (class "Default")
      (node (ref "JP4") (pin "25") (pinfunction "25_25") (pintype "passive"))
    )
    (net (code "92") (name "/REL3") (class "Default")
      (node (ref "JP4") (pin "26") (pinfunction "26_26") (pintype "passive"))
    )
    (net (code "93") (name "/REL4") (class "Default")
      (node (ref "JP4") (pin "27") (pinfunction "27_27") (pintype "passive"))
    )
    (net (code "94") (name "/REL5") (class "Default")
      (node (ref "JP4") (pin "28") (pinfunction "28_28") (pintype "passive"))
    )
    (net (code "95") (name "/REL6") (class "Default")
      (node (ref "JP4") (pin "29") (pinfunction "29_29") (pintype "passive"))
    )
    (net (code "96") (name "/REL7") (class "Default")
      (node (ref "JP4") (pin "16") (pinfunction "16_16") (pintype "passive"))
    )
    (net (code "97") (name "/RES") (class "Default")
      (node (ref "D1") (pin "1") (pinfunction "A_1") (pintype "passive"))
      (node (ref "JP6") (pin "8") (pinfunction "8_8") (pintype "passive"))
      (node (ref "U13") (pin "17") (pinfunction "~{RESET}_17") (pintype "passive"))
    )
    (net (code "98") (name "/SK1") (class "Default")
      (node (ref "JP4") (pin "23") (pinfunction "23_23") (pintype "passive"))
    )
    (net (code "99") (name "/SK2") (class "Default")
      (node (ref "JP4") (pin "22") (pinfunction "22_22") (pintype "passive"))
    )
    (net (code "100") (name "/SK3") (class "Default")
      (node (ref "JP4") (pin "21") (pinfunction "21_21") (pintype "passive"))
    )
    (net (code "101") (name "/SK4") (class "Default")
      (node (ref "JP4") (pin "20") (pinfunction "20_20") (pintype "passive"))
    )
    (net (code "102") (name "/Ub1") (class "Default")
      (node (ref "JP4") (pin "3") (pinfunction "3_3") (pintype "passive"))
    )
    (net (code "103") (name "/Ub2") (class "Default")
      (node (ref "JP4") (pin "5") (pinfunction "5_5") (pintype "passive"))
    )
    (net (code "104") (name "/Ubm1") (class "Default")
      (node (ref "JP4") (pin "4") (pinfunction "4_4") (pintype "passive"))
      (node (ref "R102") (pin "1") (pinfunction "1_1") (pintype "passive"))
    )
    (net (code "105") (name "/Ubm2") (class "Default")
      (node (ref "JP4") (pin "6") (pinfunction "6_6") (pintype "passive"))
    )
    (net (code "106") (name "/Uib1") (class "Default")
      (node (ref "U24") (pin "7") (pinfunction "AIN1(+)_7") (pintype "passive"))
    )
    (net (code "107") (name "/Uib2") (class "Default")
      (node (ref "U24") (pin "6") (pinfunction "AIN2(+)_6") (pintype "passive"))
    )
    (net (code "108") (name "/Uload") (class "Default")
      (node (ref "JP4") (pin "19") (pinfunction "19_19") (pintype "passive"))
    )
    (net (code "109") (name "/Us") (class "Default")
      (node (ref "JP4") (pin "7") (pinfunction "7_7") (pintype "passive"))
    )
    (net (code "110") (name "/Vs") (class "Default")
      (node (ref "JP4") (pin "8") (pinfunction "8_8") (pintype "passive"))
    )
    (net (code "111") (name "GND") (class "Default")
      (node (ref "C1") (pin "2") (pinfunction "2_2") (pintype "passive"))
      (node (ref "C2") (pin "1") (pinfunction "1_1") (pintype "passive"))
      (node (ref "C200") (pin "1") (pinfunction "1_1") (pintype "passive"))
      (node (ref "C201") (pin "1") (pinfunction "1_1") (pintype "passive"))
      (node (ref "C22") (pin "1") (pinfunction "1_1") (pintype "passive"))
      (node (ref "C3") (pin "2") (pinfunction "2_2") (pintype "passive"))
      (node (ref "C35") (pin "1") (pinfunction "1_1") (pintype "passive"))
      (node (ref "C36") (pin "1") (pinfunction "1_1") (pintype "passive"))
      (node (ref "C50") (pin "1") (pinfunction "1_1") (pintype "passive"))
      (node (ref "C51") (pin "1") (pinfunction "1_1") (pintype "passive"))
      (node (ref "C52") (pin "1") (pinfunction "1_1") (pintype "passive"))
      (node (ref "C53") (pin "1") (pinfunction "1_1") (pintype "passive"))
      (node (ref "C54") (pin "1") (pinfunction "1_1") (pintype "passive"))
      (node (ref "C55") (pin "1") (pinfunction "1_1") (pintype "passive"))
      (node (ref "C56") (pin "1") (pinfunction "1_1") (pintype "passive"))
      (node (ref "C57") (pin "1") (pinfunction "1_1") (pintype "passive"))
      (node (ref "C58") (pin "1") (pinfunction "1_1") (pintype "passive"))
      (node (ref "C60") (pin "1") (pinfunction "1_1") (pintype "passive"))
      (node (ref "JP1") (pin "7") (pinfunction "7_7") (pintype "passive"))
      (node (ref "JP4") (pin "14") (pinfunction "14_14") (pintype "passive"))
      (node (ref "JP6") (pin "1") (pinfunction "1_1") (pintype "passive"))
      (node (ref "JP6") (pin "2") (pinfunction "2_2") (pintype "passive"))
      (node (ref "Q4") (pin "2") (pinfunction "E_2") (pintype "passive"))
      (node (ref "R18") (pin "2") (pinfunction "2_2") (pintype "passive"))
      (node (ref "R19") (pin "1") (pinfunction "1_1") (pintype "passive"))
      (node (ref "R23") (pin "1") (pinfunction "1_1") (pintype "passive"))
      (node (ref "U1") (pin "6") (pinfunction "Vss_6") (pintype "passive"))
      (node (ref "U1") (pin "8") (pinfunction "~{SPI}_8") (pintype "passive"))
      (node (ref "U1") (pin "9") (pinfunction "Vss_9") (pintype "passive"))
      (node (ref "U11") (pin "2") (pinfunction "GND_2") (pintype "passive"))
      (node (ref "U11") (pin "8") (pinfunction "S_8") (pintype "passive"))
      (node (ref "U13") (pin "11") (pinfunction "Vssa_11") (pintype "passive"))
      (node (ref "U13") (pin "15") (pinfunction "Vss_15") (pintype "passive"))
      (node (ref "U13") (pin "31") (pinfunction "Vss_31") (pintype "passive"))
      (node (ref "U13") (pin "41") (pinfunction "Vss_41") (pintype "passive"))
      (node (ref "U13") (pin "55") (pinfunction "Vss_55") (pintype "passive"))
      (node (ref "U13") (pin "72") (pinfunction "Vss_72") (pintype "passive"))
      (node (ref "U13") (pin "83") (pinfunction "Vss_83") (pintype "passive"))
      (node (ref "U13") (pin "97") (pinfunction "Vss_97") (pintype "passive"))
      (node (ref "U23") (pin "4") (pinfunction "Vss_4") (pintype "passive"))
      (node (ref "U24") (pin "10") (pinfunction "REF_IN(-)_10") (pintype "passive"))
      (node (ref "U24") (pin "11") (pinfunction "AIN2(-)_11") (pintype "passive"))
      (node (ref "U24") (pin "16") (pinfunction "GND_16") (pintype "passive"))
      (node (ref "U24") (pin "8") (pinfunction "AIN1(-)_8") (pintype "passive"))
      (node (ref "U4") (pin "10") (pinfunction "GND_10") (pintype "passive"))
      (node (ref "U5") (pin "2") (pinfunction "GND_2") (pintype "power_in"))
      (node (ref "X11") (pin "1") (pinfunction "1_1") (pintype "passive"))
      (node (ref "X9") (pin "1") (pinfunction "1_1") (pintype "passive"))
    )
    (net (code "112") (name "Net-(A1-Pad2)") (class "Default")
      (node (ref "A1") (pin "2") (pinfunction "2_2") (pintype "passive"))
      (node (ref "C3") (pin "1") (pinfunction "1_1") (pintype "passive"))
      (node (ref "R103") (pin "1") (pinfunction "1_1") (pintype "passive"))
      (node (ref "R16") (pin "1") (pinfunction "1_1") (pintype "passive"))
      (node (ref "R19") (pin "2") (pinfunction "2_2") (pintype "passive"))
    )
    (net (code "113") (name "Net-(D1-K)") (class "Default")
      (node (ref "D1") (pin "2") (pinfunction "K_2") (pintype "passive"))
      (node (ref "X18") (pin "1") (pinfunction "1_1") (pintype "passive"))
    )
    (net (code "114") (name "Net-(Q4-B)") (class "Default")
      (node (ref "Q4") (pin "1") (pinfunction "B_1") (pintype "passive"))
      (node (ref "R22") (pin "2") (pinfunction "2_2") (pintype "passive"))
      (node (ref "R23") (pin "2") (pinfunction "2_2") (pintype "passive"))
    )
    (net (code "115") (name "Net-(Q4-C)") (class "Default")
      (node (ref "A1") (pin "1") (pinfunction "1_1") (pintype "passive"))
      (node (ref "Q4") (pin "3") (pinfunction "C_3") (pintype "passive"))
    )
    (net (code "116") (name "Net-(U1-XTAL1)") (class "Default")
      (node (ref "C201") (pin "2") (pinfunction "2_2") (pintype "passive"))
      (node (ref "U1") (pin "15") (pinfunction "XTAL1_15") (pintype "passive"))
      (node (ref "Y2") (pin "1") (pinfunction "OSC1_1") (pintype "passive"))
    )
    (net (code "117") (name "Net-(U1-XTAL2)") (class "Default")
      (node (ref "C200") (pin "2") (pinfunction "2_2") (pintype "passive"))
      (node (ref "U1") (pin "16") (pinfunction "XTAL2_16") (pintype "passive"))
      (node (ref "Y2") (pin "2") (pinfunction "OSC2_2") (pintype "passive"))
    )
    (net (code "118") (name "Net-(U4-OSC1)") (class "Default")
      (node (ref "C22") (pin "2") (pinfunction "2_2") (pintype "passive"))
      (node (ref "U4") (pin "9") (pinfunction "OSC1_9") (pintype "passive"))
      (node (ref "Y5") (pin "1") (pinfunction "OSC1_1") (pintype "passive"))
    )
    (net (code "119") (name "Net-(U4-OSC2)") (class "Default")
      (node (ref "C2") (pin "2") (pinfunction "2_2") (pintype "passive"))
      (node (ref "U4") (pin "8") (pinfunction "OSC2_8") (pintype "passive"))
      (node (ref "Y5") (pin "2") (pinfunction "OSC2_2") (pintype "passive"))
    )
    (net (code "120") (name "Net-(U11-RXD)") (class "Default")
      (node (ref "U11") (pin "4") (pinfunction "RXD_4") (pintype "passive"))
      (node (ref "U4") (pin "2") (pinfunction "RXCAN_2") (pintype "passive"))
    )
    (net (code "121") (name "Net-(U11-TXD)") (class "Default")
      (node (ref "U11") (pin "1") (pinfunction "TXD_1") (pintype "passive"))
      (node (ref "U4") (pin "1") (pinfunction "TXCAN_1") (pintype "passive"))
    )
    (net (code "122") (name "Net-(U13-RTCX1)") (class "Default")
      (node (ref "C35") (pin "2") (pinfunction "2_2") (pintype "passive"))
      (node (ref "U13") (pin "16") (pinfunction "RTCX1_16") (pintype "passive"))
      (node (ref "Y1") (pin "2") (pinfunction "OSC2_2") (pintype "passive"))
    )
    (net (code "123") (name "Net-(U13-RTCX2)") (class "Default")
      (node (ref "C36") (pin "2") (pinfunction "2_2") (pintype "passive"))
      (node (ref "U13") (pin "18") (pinfunction "RTCX2_18") (pintype "passive"))
      (node (ref "Y1") (pin "1") (pinfunction "OSC1_1") (pintype "passive"))
    )
    (net (code "124") (name "Net-(U13-XTAL1)") (class "Default")
      (node (ref "C52") (pin "2") (pinfunction "2_2") (pintype "passive"))
      (node (ref "U13") (pin "22") (pinfunction "XTAL1_22") (pintype "passive"))
      (node (ref "Y3") (pin "2") (pinfunction "OSC2_2") (pintype "passive"))
    )
    (net (code "125") (name "Net-(U13-XTAL2)") (class "Default")
      (node (ref "C51") (pin "2") (pinfunction "2_2") (pintype "passive"))
      (node (ref "U13") (pin "23") (pinfunction "XTAL2_23") (pintype "passive"))
      (node (ref "Y3") (pin "1") (pinfunction "OSC1_1") (pintype "passive"))
    )
    (net (code "126") (name "Net-(U23-~{HOLD})") (class "Default")
      (node (ref "R96") (pin "2") (pinfunction "2_2") (pintype "passive"))
      (node (ref "U23") (pin "7") (pinfunction "~{HOLD}_7") (pintype "passive"))
    )
    (net (code "127") (name "Net-(U23-~{WP})") (class "Default")
      (node (ref "R95") (pin "1") (pinfunction "1_1") (pintype "passive"))
      (node (ref "U23") (pin "3") (pinfunction "~{WP}_3") (pintype "passive"))
    )
    (net (code "128") (name "Net-(U24-MCLK_IN)") (class "Default")
      (node (ref "C50") (pin "2") (pinfunction "2_2") (pintype "passive"))
      (node (ref "U24") (pin "2") (pinfunction "MCLK_IN_2") (pintype "passive"))
      (node (ref "Y4") (pin "1") (pinfunction "OSC1_1") (pintype "passive"))
    )
    (net (code "129") (name "Net-(U24-MCLK_OUT)") (class "Default")
      (node (ref "C53") (pin "2") (pinfunction "2_2") (pintype "passive"))
      (node (ref "U24") (pin "3") (pinfunction "MCLK_OUT_3") (pintype "passive"))
      (node (ref "Y4") (pin "2") (pinfunction "OSC2_2") (pintype "passive"))
    )
    (net (code "130") (name "Net-(X16-Pad1)") (class "Default")
      (node (ref "X16") (pin "1") (pinfunction "1_1") (pintype "passive"))
      (node (ref "X22") (pin "1") (pinfunction "1_1") (pintype "passive"))
    )
    (net (code "131") (name "Net-(X21-Pad1)") (class "Default")
      (node (ref "X21") (pin "1") (pinfunction "1_1") (pintype "passive"))
      (node (ref "X23") (pin "1") (pinfunction "1_1") (pintype "passive"))
    )
    (net (code "132") (name "Net-(X24-Pad1)") (class "Default")
      (node (ref "X24") (pin "1") (pinfunction "1_1") (pintype "passive"))
      (node (ref "X26") (pin "1") (pinfunction "1_1") (pintype "passive"))
    )
    (net (code "133") (name "Net-(X25-Pad1)") (class "Default")
      (node (ref "X25") (pin "1") (pinfunction "1_1") (pintype "passive"))
      (node (ref "X27") (pin "1") (pinfunction "1_1") (pintype "passive"))
    )
    (net (code "134") (name "Vbat") (class "Default")
      (node (ref "JP1") (pin "6") (pinfunction "6_6") (pintype "passive"))
      (node (ref "U13") (pin "19") (pinfunction "VBAT_19") (pintype "passive"))
    )
    (net (code "135") (name "Vref") (class "Default")
      (node (ref "U13") (pin "10") (pinfunction "Vdda_10") (pintype "passive"))
      (node (ref "U13") (pin "12") (pinfunction "VREF_12") (pintype "passive"))
      (node (ref "U24") (pin "9") (pinfunction "REF_IN(+)_9") (pintype "passive"))
      (node (ref "U5") (pin "5") (pinfunction "OUT_5") (pintype "power_in"))
    )
    (net (code "136") (name "unconnected-(JP4-Pad30)") (class "Default")
      (node (ref "JP4") (pin "30") (pinfunction "30_30") (pintype "passive"))
    )
    (net (code "137") (name "unconnected-(JP6-Pad10)") (class "Default")
      (node (ref "JP6") (pin "10") (pinfunction "10_10") (pintype "passive"))
    )
    (net (code "138") (name "unconnected-(U1-~{CTS}-Pad11)") (class "Default")
      (node (ref "U1") (pin "11") (pinfunction "~{CTS}_11") (pintype "passive"))
    )
    (net (code "139") (name "unconnected-(U1-~{IRQ}-Pad7)") (class "Default")
      (node (ref "U1") (pin "7") (pinfunction "~{IRQ}_7") (pintype "passive"))
    )
    (net (code "140") (name "unconnected-(U4-CLKOUT-Pad3)") (class "Default")
      (node (ref "U4") (pin "3") (pinfunction "CLKOUT_3") (pintype "passive"))
    )
    (net (code "141") (name "unconnected-(U4-NC-Pad6)") (class "Default")
      (node (ref "U4") (pin "6") (pinfunction "NC_6") (pintype "passive"))
    )
    (net (code "142") (name "unconnected-(U4-NC-Pad15)") (class "Default")
      (node (ref "U4") (pin "15") (pinfunction "NC_15") (pintype "passive"))
    )
    (net (code "143") (name "unconnected-(U4-~{INT}-Pad13)") (class "Default")
      (node (ref "U4") (pin "13") (pinfunction "~{INT}_13") (pintype "passive"))
    )
    (net (code "144") (name "unconnected-(U4-~{RX0BF}-Pad12)") (class "Default")
      (node (ref "U4") (pin "12") (pinfunction "~{RX0BF}_12") (pintype "passive"))
    )
    (net (code "145") (name "unconnected-(U4-~{RX1BF}-Pad11)") (class "Default")
      (node (ref "U4") (pin "11") (pinfunction "~{RX1BF}_11") (pintype "passive"))
    )
    (net (code "146") (name "unconnected-(U4-~{TX0RTS}-Pad4)") (class "Default")
      (node (ref "U4") (pin "4") (pinfunction "~{TX0RTS}_4") (pintype "passive"))
    )
    (net (code "147") (name "unconnected-(U4-~{TX1RTS}-Pad5)") (class "Default")
      (node (ref "U4") (pin "5") (pinfunction "~{TX1RTS}_5") (pintype "passive"))
    )
    (net (code "148") (name "unconnected-(U4-~{TX2RTS}-Pad7)") (class "Default")
      (node (ref "U4") (pin "7") (pinfunction "~{TX2RTS}_7") (pintype "passive"))
    )
    (net (code "149") (name "unconnected-(U5-NC-Pad4)") (class "Default")
      (node (ref "U5") (pin "4") (pinfunction "NC_4") (pintype "passive"))
    )
    (net (code "150") (name "unconnected-(U11-Vref-Pad5)") (class "Default")
      (node (ref "U11") (pin "5") (pinfunction "Vref_5") (pintype "passive"))
    )
    (net (code "151") (name "unconnected-(U13-RTCK-Pad100)") (class "Default")
      (node (ref "U13") (pin "100") (pinfunction "RTCK_100") (pintype "passive"))
    )
    (net (code "152") (name "unconnected-(U13-TCK-Pad5)") (class "Default")
      (node (ref "U13") (pin "5") (pinfunction "TCK_5") (pintype "passive"))
    )
    (net (code "153") (name "unconnected-(U13-TDI-Pad2)") (class "Default")
      (node (ref "U13") (pin "2") (pinfunction "TDI_2") (pintype "passive"))
    )
    (net (code "154") (name "unconnected-(U13-TDO-Pad1)") (class "Default")
      (node (ref "U13") (pin "1") (pinfunction "TDO_1") (pintype "passive"))
    )
    (net (code "155") (name "unconnected-(U13-TMS-Pad3)") (class "Default")
      (node (ref "U13") (pin "3") (pinfunction "TMS_3") (pintype "passive"))
    )
    (net (code "156") (name "unconnected-(U13-~{RSTOUT}-Pad14)") (class "Default")
      (node (ref "U13") (pin "14") (pinfunction "~{RSTOUT}_14") (pintype "passive"))
    )
    (net (code "157") (name "unconnected-(U13-~{TRST}-Pad4)") (class "Default")
      (node (ref "U13") (pin "4") (pinfunction "~{TRST}_4") (pintype "passive"))
    )
    (net (code "158") (name "unconnected-(U24-~{DRDY}-Pad12)") (class "Default")
      (node (ref "U24") (pin "12") (pinfunction "~{DRDY}_12") (pintype "passive"))
    )
  )
)
